# Display.net
KiCad netlist of a schematic drawn in Altium Designer
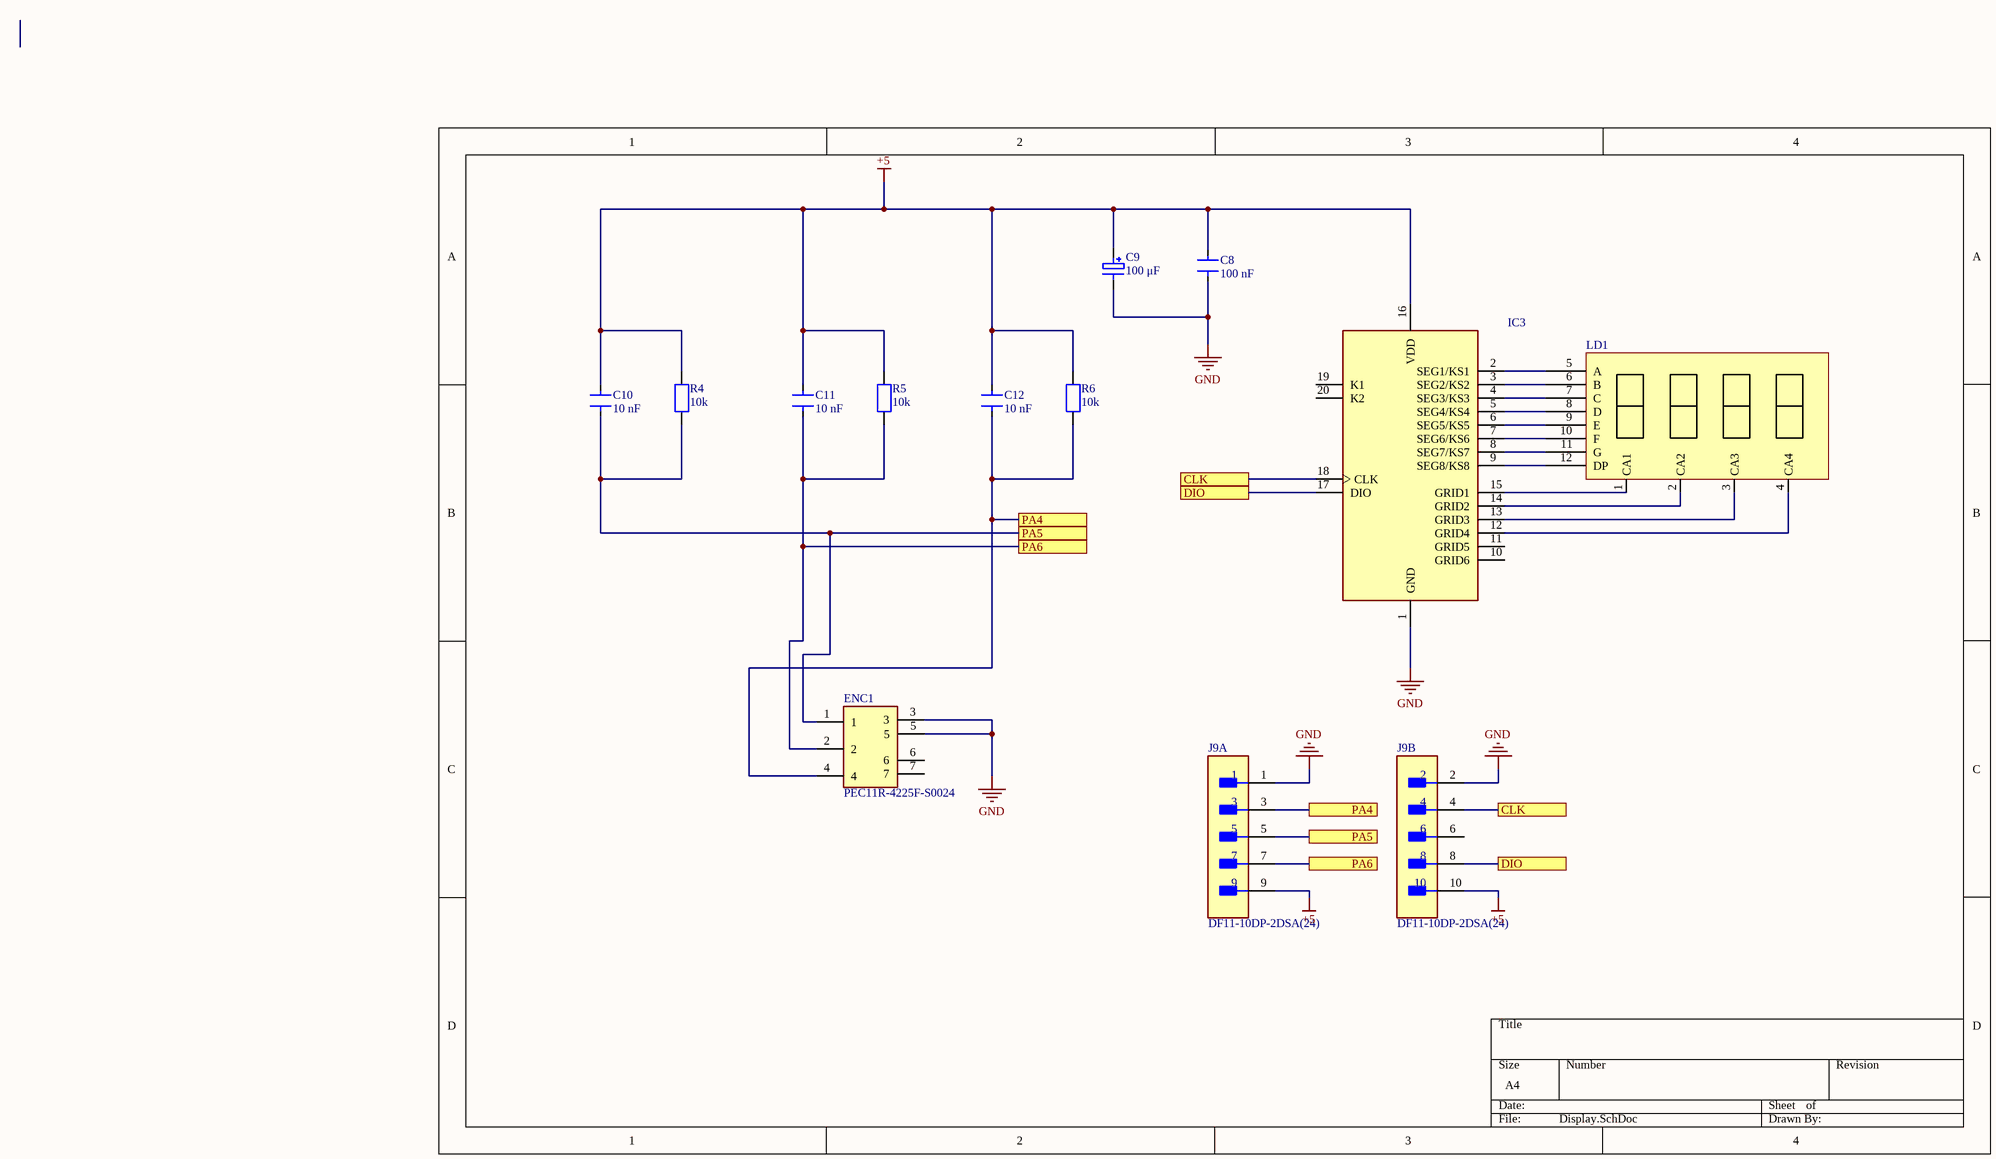
[diagram p0: Display.SchDoc]

(export (version "E")
  (design (tool "Eeschema 10.0.6"))
  (components
    (comp (ref "C8")
      (value "100 nF")
      (footprint "0805")
      (description "Chip Multilayer Ceramic Capacitors for General Purpose, 0805, 10uF, X5R, 15%, 10%, 25V")
      (fields (field (name "VOLTAGE") "25V") (field (name "TOLERANCE") "10%"))
      (libsource (lib "Soldeerstation") (part "Condensator 0805"))
    )
    (comp (ref "C9")
      (value "100 μF")
      (footprint "Elco 100uF 25V")
      (fields
        (field (name "PART NUMBER") "02015A270JAT2A")
        (field (name "MANUFACTURER") "AVX Interconnect / Elco")
      )
      (libsource (lib "Soldeerstation") (part "Condensator Elco"))
    )
    (comp (ref "C10")
      (value "10 nF")
      (footprint "0805")
      (description "Chip Multilayer Ceramic Capacitors for General Purpose, 0805, 10uF, X5R, 15%, 10%, 25V")
      (fields (field (name "VOLTAGE") "25V") (field (name "TOLERANCE") "10%"))
      (libsource (lib "Soldeerstation") (part "Condensator 0805"))
    )
    (comp (ref "C11")
      (value "10 nF")
      (footprint "0805")
      (description "Chip Multilayer Ceramic Capacitors for General Purpose, 0805, 10uF, X5R, 15%, 10%, 25V")
      (fields (field (name "VOLTAGE") "25V") (field (name "TOLERANCE") "10%"))
      (libsource (lib "Soldeerstation") (part "Condensator 0805"))
    )
    (comp (ref "C12")
      (value "10 nF")
      (footprint "0805")
      (description "Chip Multilayer Ceramic Capacitors for General Purpose, 0805, 10uF, X5R, 15%, 10%, 25V")
      (fields (field (name "VOLTAGE") "25V") (field (name "TOLERANCE") "10%"))
      (libsource (lib "Soldeerstation") (part "Condensator 0805"))
    )
    (comp (ref "ENC1")
      (value "PEC11R-4225F-S0024")
      (footprint "Encoder")
      (description "Undefined or Miscellaneous")
      (fields (field (name "MOUSER2 PART NUMBER") "652-PEC11R-4225F-S24"))
      (libsource (lib "Soldeerstation") (part "Encoder"))
    )
    (comp (ref "IC3")
      (value "TM1637")
      (footprint "TM1637")
      (description "LED Drive Control Special Circuit")
      (fields (field (name "MF") "Titan Micro Electronics"))
      (libsource (lib "Soldeerstation") (part "TM1637"))
    )
    (comp (ref "J9")
      (value "DF11-10DP-2DSA(24)")
      (footprint "FP-DF11-10DP-2DSA_24-MFG")
      (description "CONN HEADER VERT 10POS 2MM")
      (fields
        (field (name "OCTOPART") "https://octopart.com/df11-10dp-2dsa%2824%29-hirose-39521433")
        (field (name "MANUFACTURER") "Hirose")
      )
      (libsource (lib "Soldeerstation") (part "CMP-11610-000008-1"))
    )
    (comp (ref "LD1")
      (value "7segment")
      (footprint "7segment")
      (libsource (lib "Soldeerstation") (part "7segment"))
    )
    (comp (ref "R4")
      (value "10k")
      (footprint "Resistor")
      (description "Resistor")
      (fields (field (name "MANUFACTURER") "Vishay Dale") (field (name "PART NUMBER") "CRCW08050000Z0EA"))
      (libsource (lib "Soldeerstation") (part "Resistor"))
    )
    (comp (ref "R5")
      (value "10k")
      (footprint "Resistor")
      (description "Resistor")
      (fields (field (name "MANUFACTURER") "Vishay Dale") (field (name "PART NUMBER") "CRCW08050000Z0EA"))
      (libsource (lib "Soldeerstation") (part "Resistor"))
    )
    (comp (ref "R6")
      (value "10k")
      (footprint "Resistor")
      (description "Resistor")
      (fields (field (name "MANUFACTURER") "Vishay Dale") (field (name "PART NUMBER") "CRCW08050000Z0EA"))
      (libsource (lib "Soldeerstation") (part "Resistor"))
    )
  )
  (nets
    (net (code "1") (name "+5") (class "Default")
      (node (ref "C10") (pin "2") (pinfunction "2_2") (pintype "passive"))
      (node (ref "C11") (pin "2") (pinfunction "2_2") (pintype "passive"))
      (node (ref "C12") (pin "2") (pinfunction "2_2") (pintype "passive"))
      (node (ref "C8") (pin "2") (pinfunction "2_2") (pintype "passive"))
      (node (ref "C9") (pin "1") (pinfunction "1_1") (pintype "passive"))
      (node (ref "IC3") (pin "16") (pinfunction "VDD_16") (pintype "power_in"))
      (node (ref "J9") (pin "10") (pinfunction "10_10") (pintype "passive"))
      (node (ref "J9") (pin "9") (pinfunction "9_9") (pintype "passive"))
      (node (ref "R4") (pin "2") (pinfunction "2_2") (pintype "passive"))
      (node (ref "R5") (pin "2") (pinfunction "2_2") (pintype "passive"))
      (node (ref "R6") (pin "2") (pinfunction "2_2") (pintype "passive"))
    )
    (net (code "2") (name "/CLK") (class "Default")
      (node (ref "IC3") (pin "18") (pinfunction "CLK_18") (pintype "passive"))
      (node (ref "J9") (pin "4") (pinfunction "4_4") (pintype "passive"))
    )
    (net (code "3") (name "/DIO") (class "Default")
      (node (ref "IC3") (pin "17") (pinfunction "DIO_17") (pintype "passive"))
      (node (ref "J9") (pin "8") (pinfunction "8_8") (pintype "passive"))
    )
    (net (code "4") (name "/PA4") (class "Default")
      (node (ref "C12") (pin "1") (pinfunction "1_1") (pintype "passive"))
      (node (ref "ENC1") (pin "4") (pinfunction "4_4") (pintype "passive"))
      (node (ref "J9") (pin "3") (pinfunction "3_3") (pintype "passive"))
      (node (ref "R6") (pin "1") (pintype "passive"))
    )
    (net (code "5") (name "/PA5") (class "Default")
      (node (ref "C10") (pin "1") (pinfunction "1_1") (pintype "passive"))
      (node (ref "ENC1") (pin "1") (pinfunction "1_1") (pintype "passive"))
      (node (ref "J9") (pin "5") (pinfunction "5_5") (pintype "passive"))
      (node (ref "R4") (pin "1") (pintype "passive"))
    )
    (net (code "6") (name "/PA6") (class "Default")
      (node (ref "C11") (pin "1") (pinfunction "1_1") (pintype "passive"))
      (node (ref "ENC1") (pin "2") (pinfunction "2_2") (pintype "passive"))
      (node (ref "J9") (pin "7") (pinfunction "7_7") (pintype "passive"))
      (node (ref "R5") (pin "1") (pintype "passive"))
    )
    (net (code "7") (name "GND") (class "Default")
      (node (ref "C8") (pin "1") (pinfunction "1_1") (pintype "passive"))
      (node (ref "C9") (pin "2") (pinfunction "2_2") (pintype "passive"))
      (node (ref "ENC1") (pin "3") (pinfunction "3_3") (pintype "passive"))
      (node (ref "ENC1") (pin "5") (pinfunction "5_5") (pintype "passive"))
      (node (ref "IC3") (pin "1") (pinfunction "GND_1") (pintype "power_in"))
      (node (ref "J9") (pin "1") (pinfunction "1_1") (pintype "passive"))
      (node (ref "J9") (pin "2") (pinfunction "2_2") (pintype "passive"))
    )
    (net (code "8") (name "Net-(IC3-GRID1)") (class "Default")
      (node (ref "IC3") (pin "15") (pinfunction "GRID1_15") (pintype "passive"))
      (node (ref "LD1") (pin "1") (pinfunction "CA1_1") (pintype "power_in"))
    )
    (net (code "9") (name "Net-(IC3-GRID2)") (class "Default")
      (node (ref "IC3") (pin "14") (pinfunction "GRID2_14") (pintype "passive"))
      (node (ref "LD1") (pin "2") (pinfunction "CA2_2") (pintype "power_in"))
    )
    (net (code "10") (name "Net-(IC3-GRID3)") (class "Default")
      (node (ref "IC3") (pin "13") (pinfunction "GRID3_13") (pintype "passive"))
      (node (ref "LD1") (pin "3") (pinfunction "CA3_3") (pintype "power_in"))
    )
    (net (code "11") (name "Net-(IC3-GRID4)") (class "Default")
      (node (ref "IC3") (pin "12") (pinfunction "GRID4_12") (pintype "passive"))
      (node (ref "LD1") (pin "4") (pinfunction "CA4_4") (pintype "power_in"))
    )
    (net (code "12") (name "Net-(IC3-SEG1{slash}KS1)") (class "Default")
      (node (ref "IC3") (pin "2") (pinfunction "SEG1/KS1_2") (pintype "passive"))
      (node (ref "LD1") (pin "5") (pinfunction "A_5") (pintype "passive"))
    )
    (net (code "13") (name "Net-(IC3-SEG2{slash}KS2)") (class "Default")
      (node (ref "IC3") (pin "3") (pinfunction "SEG2/KS2_3") (pintype "passive"))
      (node (ref "LD1") (pin "6") (pinfunction "B_6") (pintype "passive"))
    )
    (net (code "14") (name "Net-(IC3-SEG3{slash}KS3)") (class "Default")
      (node (ref "IC3") (pin "4") (pinfunction "SEG3/KS3_4") (pintype "passive"))
      (node (ref "LD1") (pin "7") (pinfunction "C_7") (pintype "passive"))
    )
    (net (code "15") (name "Net-(IC3-SEG4{slash}KS4)") (class "Default")
      (node (ref "IC3") (pin "5") (pinfunction "SEG4/KS4_5") (pintype "passive"))
      (node (ref "LD1") (pin "8") (pinfunction "D_8") (pintype "passive"))
    )
    (net (code "16") (name "Net-(IC3-SEG5{slash}KS5)") (class "Default")
      (node (ref "IC3") (pin "6") (pinfunction "SEG5/KS5_6") (pintype "passive"))
      (node (ref "LD1") (pin "9") (pinfunction "E_9") (pintype "passive"))
    )
    (net (code "17") (name "Net-(IC3-SEG6{slash}KS6)") (class "Default")
      (node (ref "IC3") (pin "7") (pinfunction "SEG6/KS6_7") (pintype "passive"))
      (node (ref "LD1") (pin "10") (pinfunction "F_10") (pintype "passive"))
    )
    (net (code "18") (name "Net-(IC3-SEG7{slash}KS7)") (class "Default")
      (node (ref "IC3") (pin "8") (pinfunction "SEG7/KS7_8") (pintype "passive"))
      (node (ref "LD1") (pin "11") (pinfunction "G_11") (pintype "passive"))
    )
    (net (code "19") (name "Net-(IC3-SEG8{slash}KS8)") (class "Default")
      (node (ref "IC3") (pin "9") (pinfunction "SEG8/KS8_9") (pintype "passive"))
      (node (ref "LD1") (pin "12") (pinfunction "DP_12") (pintype "power_in"))
    )
    (net (code "20") (name "unconnected-(ENC1-Pad6)") (class "Default")
      (node (ref "ENC1") (pin "6") (pinfunction "6_6") (pintype "passive"))
    )
    (net (code "21") (name "unconnected-(ENC1-Pad7)") (class "Default")
      (node (ref "ENC1") (pin "7") (pinfunction "7_7") (pintype "passive"))
    )
    (net (code "22") (name "unconnected-(IC3-GRID5-Pad11)") (class "Default")
      (node (ref "IC3") (pin "11") (pinfunction "GRID5_11") (pintype "passive"))
    )
    (net (code "23") (name "unconnected-(IC3-GRID6-Pad10)") (class "Default")
      (node (ref "IC3") (pin "10") (pinfunction "GRID6_10") (pintype "passive"))
    )
    (net (code "24") (name "unconnected-(IC3-K1-Pad19)") (class "Default")
      (node (ref "IC3") (pin "19") (pinfunction "K1_19") (pintype "passive"))
    )
    (net (code "25") (name "unconnected-(IC3-K2-Pad20)") (class "Default")
      (node (ref "IC3") (pin "20") (pinfunction "K2_20") (pintype "passive"))
    )
    (net (code "26") (name "unconnected-(J9-Pad6)") (class "Default")
      (node (ref "J9") (pin "6") (pinfunction "6_6") (pintype "passive"))
    )
  )
)
